# 3V3.net
KiCad netlist of a schematic drawn in Altium Designer
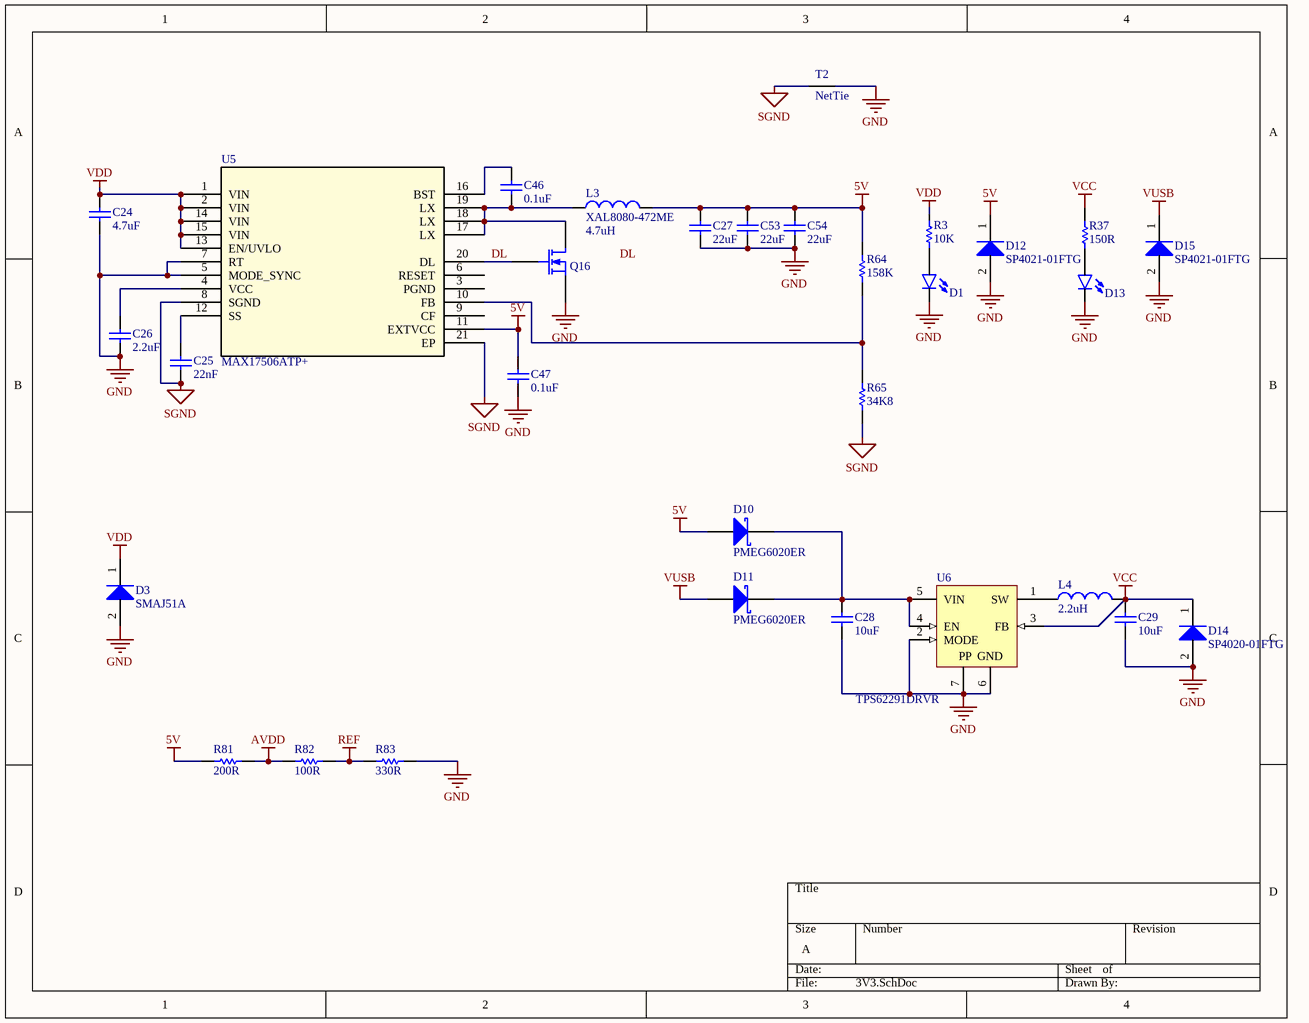
[diagram p0: 3V3.SchDoc]

(export (version "E")
  (design (tool "Eeschema 10.0.6"))
  (components
    (comp (ref "C24")
      (value "4.7uF")
      (footprint "C1210[3225X200]")
      (description "4.7uF 100V 10% 1210 (3225 Metric)")
      (fields (field (name "PARTNUMBER") "GRJ32DC72A475KE11L") (field (name "MANUFACTURER") "Murata"))
      (libsource (lib "Capacitors") (part "CAP_4.7uF_100V_1210_10%"))
    )
    (comp (ref "C25")
      (value "22nF")
      (footprint "C0603[1608X92]")
      (description "22nF 50V 10% 0603 (1608 Metric)")
      (fields (field (name "PARTNUMBER") "GRM188R71H223KA01D") (field (name "MANUFACTURER") "Murata"))
      (libsource (lib "Capacitors") (part "CAP_22nF_50V_0603_10%"))
    )
    (comp (ref "C26")
      (value "2.2uF")
      (footprint "C0603[1608X92]")
      (description "2.2uF 10V 10% 0603 (1608 Metric)")
      (fields (field (name "PARTNUMBER") "GRT188R61A225KE13D") (field (name "MANUFACTURER") "Murata"))
      (libsource (lib "Capacitors") (part "CAP_2.2uF_10V_0603_10%"))
    )
    (comp (ref "C27")
      (value "22uF")
      (footprint "C1210[3225X250]")
      (description "22uF 16V 20% 1210 (3225 Metric)")
      (fields (field (name "PARTNUMBER") "GRM32ER61C476ME15L") (field (name "MANUFACTURER") "Murata"))
      (libsource (lib "Capacitors") (part "CAP_22uF_16V_1210_20%"))
    )
    (comp (ref "C28")
      (value "10uF")
      (footprint "C0603[1608X92]")
      (description "10uF 16V 10% 0603 (1608 Metric)")
      (fields (field (name "PARTNUMBER") "GRM188R61C106KAALD") (field (name "MANUFACTURER") "Murata"))
      (libsource (lib "Capacitors") (part "CAP_10uF_16V_0603_10%"))
    )
    (comp (ref "C29")
      (value "10uF")
      (footprint "C0603[1608X92]")
      (description "10uF 6.3V 10% 0603 (1608 Metric)")
      (fields (field (name "PARTNUMBER") "GRM188R60J106KE47D") (field (name "MANUFACTURER") "Murata"))
      (libsource (lib "Capacitors") (part "CAP_10uF_6.3V_0603_10%"))
    )
    (comp (ref "C46")
      (value "0.1uF")
      (footprint "C0603[1608X92]")
      (description "0.1uF 16V 10% 0603 (1608 Metric)")
      (fields (field (name "PARTNUMBER") "GCM188R71C104KA37D") (field (name "MANUFACTURER") "Murata"))
      (libsource (lib "Capacitors") (part "CAP_0.1uF_16V_0603_10%"))
    )
    (comp (ref "C47")
      (value "0.1uF")
      (footprint "C0603[1608X92]")
      (description "0.1uF 6.3V 10% 0603 (1608 Metric)")
      (fields (field (name "PARTNUMBER") "GRM188R70J104KA01D") (field (name "MANUFACTURER") "Murata"))
      (libsource (lib "Capacitors") (part "CAP_0.1uF_6.3V_0603_10%"))
    )
    (comp (ref "C53")
      (value "22uF")
      (footprint "C1210[3225X250]")
      (description "22uF 16V 20% 1210 (3225 Metric)")
      (fields (field (name "PARTNUMBER") "GRM32ER61C476ME15L") (field (name "MANUFACTURER") "Murata"))
      (libsource (lib "Capacitors") (part "CAP_22uF_16V_1210_20%"))
    )
    (comp (ref "C54")
      (value "22uF")
      (footprint "C1210[3225X250]")
      (description "22uF 16V 20% 1210 (3225 Metric)")
      (fields (field (name "PARTNUMBER") "GRM32ER61C476ME15L") (field (name "MANUFACTURER") "Murata"))
      (libsource (lib "Capacitors") (part "CAP_22uF_16V_1210_20%"))
    )
    (comp (ref "D1")
      (value "LED_0603_GREEN_5mA")
      (footprint "LED0603")
      (fields (field (name "PARTNUMBER") "LTST-C193TGKT-5A") (field (name "MANUFACTURER") "Lite-On Inc."))
      (libsource (lib "LEDs") (part "LED_0603_GREEN_5mA"))
    )
    (comp (ref "D3")
      (value "SMAJ51A")
      (footprint "DO-214AC")
      (fields (field (name "PARTNUMBER") "SMAJ51A-E3/61") (field (name "MANUFACTURER") "Vishay"))
      (libsource (lib "Diodes") (part "SMAJ51A-E3/61"))
    )
    (comp (ref "D10")
      (value "PMEG6020ER")
      (footprint "SOD-123")
      (fields (field (name "PARTNUMBER") "PMEG6020ER,115") (field (name "MANUFACTURER") "NXP Semiconductors"))
      (libsource (lib "Diodes") (part "PMEG6020ER"))
    )
    (comp (ref "D11")
      (value "PMEG6020ER")
      (footprint "SOD-123")
      (fields (field (name "PARTNUMBER") "PMEG6020ER,115") (field (name "MANUFACTURER") "NXP Semiconductors"))
      (libsource (lib "Diodes") (part "PMEG6020ER"))
    )
    (comp (ref "D12")
      (value "SP4021-01FTG")
      (footprint "SOD-323")
      (fields (field (name "MANUFACTURER") "Littelfuse"))
      (libsource (lib "Diodes") (part "SP4021-01FTG"))
    )
    (comp (ref "D13")
      (value "LED_0603_GREEN_5mA")
      (footprint "LED0603")
      (fields (field (name "PARTNUMBER") "LTST-C193TGKT-5A") (field (name "MANUFACTURER") "Lite-On Inc."))
      (libsource (lib "LEDs") (part "LED_0603_GREEN_5mA"))
    )
    (comp (ref "D14")
      (value "SP4020-01FTG")
      (footprint "SOD-323")
      (fields (field (name "MANUFACTURER") "Littelfuse"))
      (libsource (lib "Diodes") (part "SP4020-01FTG"))
    )
    (comp (ref "D15")
      (value "SP4021-01FTG")
      (footprint "SOD-323")
      (fields (field (name "MANUFACTURER") "Littelfuse"))
      (libsource (lib "Diodes-TVS") (part "SP4021-01FTG"))
    )
    (comp (ref "L3")
      (value "XAL8080-472ME")
      (footprint "XAL8080")
      (description "4.7uH 38A 4.08mOhms")
      (fields
        (field (name "ALTIUM_VALUE") "4.7uH")
        (field (name "PARTNUMBER") "XAL8080-472MED")
        (field (name "MANUFACTURER") "Coilcraft")
        (field (name "PUBLISHER") "Altium Limited")
      )
      (libsource (lib "General_Component") (part "XAL8080-472ME"))
    )
    (comp (ref "L4")
      (value "2.2uH")
      (footprint "IND0805")
      (description "2.2uH 20% 1.7A 0805")
      (fields (field (name "PARTNUMBER") "LQM21PN2R2MGHL") (field (name "MANUFACTURER") "Murata"))
      (libsource (lib "Inductors") (part "IND_2.2uH_1.7A_0805_20%"))
    )
    (comp (ref "Q16")
      (value "SIS862DN-T1-GE3")
      (footprint "PowerPak-1212-8")
      (description "N-Channel MOSFET")
      (fields (field (name "MANUFACTURER") "Vishay"))
      (libsource (lib "MOSFETs") (part "SIS862DN-T1-GE3"))
    )
    (comp (ref "R3")
      (value "10K")
      (footprint "R0603[1608]")
      (description "10K 0.25W 1% 0603 (1005 Metric)")
      (fields (field (name "TOLERANCE") "1%") (field (name "POWER") "0.25W"))
      (libsource (lib "Resistors") (part "RES_10K_0603_1%"))
    )
    (comp (ref "R37")
      (value "150R")
      (footprint "R0603[1608]")
      (description "150R 0.25W 1% 0603 (1005 Metric)")
      (fields (field (name "MANUFACTURER") "Vishay / Dale") (field (name "PARTNUMBER") "CRCW0603150RFKEAHP"))
      (libsource (lib "Resistors") (part "RES_150R_0603_1%"))
    )
    (comp (ref "R64")
      (value "158K")
      (footprint "R0603[1608]")
      (description "158K 0.25W 1% 0603 (1005 Metric)")
      (fields (field (name "MANUFACTURER") "Vishay / Dale") (field (name "PARTNUMBER") "CRCW0603158KFKEAHP"))
      (libsource (lib "Resistors") (part "RES_158K_0603_1%"))
    )
    (comp (ref "R65")
      (value "34K8")
      (footprint "R0603[1608]")
      (description "34K8 0.25W 1% 0603 (1005 Metric)")
      (fields (field (name "MANUFACTURER") "Vishay / Dale") (field (name "PARTNUMBER") "CRCW060334K8FKEAHP"))
      (libsource (lib "Resistors") (part "RES_34K8_0603_1%"))
    )
    (comp (ref "R81")
      (value "200R")
      (footprint "R0603[1608]")
      (description "200R 0.25W 1% 0603 (1005 Metric)")
      (fields (field (name "MANUFACTURER") "Vishay / Dale") (field (name "PARTNUMBER") "CRCW0603200RFKEAHP"))
      (libsource (lib "Resistors") (part "RES_200R_0603_1%"))
    )
    (comp (ref "R82")
      (value "100R")
      (footprint "R0603[1608]")
      (description "100R 0.25W 1% 0603 (1005 Metric)")
      (fields (field (name "MANUFACTURER") "Vishay / Dale") (field (name "PARTNUMBER") "CRCW0603100RFKEAHP"))
      (libsource (lib "Resistors") (part "RES_100R_0603_1%"))
    )
    (comp (ref "R83")
      (value "330R")
      (footprint "R0603[1608]")
      (description "330R 0.25W 1% 0603 (1005 Metric)")
      (fields (field (name "MANUFACTURER") "Vishay / Dale") (field (name "PARTNUMBER") "CRCW0603330RFKEAHP"))
      (libsource (lib "Resistors") (part "RES_330R_0603_1%"))
    )
    (comp (ref "T2") (value "NetTie") (footprint "NetTie") (libsource (lib "Components") (part "NetTie")))
    (comp (ref "U5")
      (value "MAX17506ATP+")
      (footprint "21-0140L_T2055-4")
      (fields (field (name "MANUFACTURER") "Maxim"))
      (libsource (lib "General_Component") (part "MAX17506ATP+"))
    )
    (comp (ref "U6")
      (value "TPS62291DRVR")
      (footprint "WSON-6")
      (description "Voltage Regulators - Switching Regulators 2.25MHz 1A Step-Down Cnvrtr 3.3V Output")
      (fields (field (name "MANUFACTURER") "Texas Instruments"))
      (libsource (lib "ICs") (part "TPS62291DRVR"))
    )
  )
  (nets
    (net (code "1") (name "/DL") (class "Default")
      (node (ref "Q16") (pin "2") (pinfunction "G_2") (pintype "passive"))
      (node (ref "U5") (pin "20") (pinfunction "DL_20") (pintype "passive"))
    )
    (net (code "2") (name "5V") (class "Default")
      (node (ref "C27") (pin "2") (pinfunction "2_2") (pintype "passive"))
      (node (ref "C47") (pin "2") (pinfunction "2_2") (pintype "passive"))
      (node (ref "C53") (pin "2") (pinfunction "2_2") (pintype "passive"))
      (node (ref "C54") (pin "2") (pinfunction "2_2") (pintype "passive"))
      (node (ref "D10") (pin "2") (pinfunction "A_2") (pintype "passive"))
      (node (ref "D12") (pin "1") (pinfunction "K_1") (pintype "passive"))
      (node (ref "L3") (pin "2") (pinfunction "2_2") (pintype "passive"))
      (node (ref "R64") (pin "2") (pinfunction "2_2") (pintype "passive"))
      (node (ref "R81") (pin "1") (pinfunction "1_1") (pintype "passive"))
      (node (ref "U5") (pin "11") (pinfunction "EXTVCC_11") (pintype "passive"))
    )
    (net (code "3") (name "AVDD") (class "Default")
      (node (ref "R81") (pin "2") (pinfunction "2_2") (pintype "passive"))
      (node (ref "R82") (pin "1") (pinfunction "1_1") (pintype "passive"))
    )
    (net (code "4") (name "GND") (class "Default")
      (node (ref "C24") (pin "1") (pinfunction "1_1") (pintype "passive"))
      (node (ref "C26") (pin "1") (pinfunction "1_1") (pintype "passive"))
      (node (ref "C27") (pin "1") (pinfunction "1_1") (pintype "passive"))
      (node (ref "C28") (pin "1") (pinfunction "1_1") (pintype "passive"))
      (node (ref "C29") (pin "1") (pinfunction "1_1") (pintype "passive"))
      (node (ref "C47") (pin "1") (pinfunction "1_1") (pintype "passive"))
      (node (ref "C53") (pin "1") (pinfunction "1_1") (pintype "passive"))
      (node (ref "C54") (pin "1") (pinfunction "1_1") (pintype "passive"))
      (node (ref "D1") (pin "C") (pinfunction "C_C") (pintype "passive"))
      (node (ref "D12") (pin "2") (pinfunction "A_2") (pintype "passive"))
      (node (ref "D13") (pin "C") (pinfunction "C_C") (pintype "passive"))
      (node (ref "D14") (pin "2") (pinfunction "A_2") (pintype "passive"))
      (node (ref "D15") (pin "2") (pinfunction "A_2") (pintype "passive"))
      (node (ref "D3") (pin "2") (pinfunction "A_2") (pintype "passive"))
      (node (ref "Q16") (pin "1") (pinfunction "S_1") (pintype "passive"))
      (node (ref "R83") (pin "2") (pinfunction "2_2") (pintype "passive"))
      (node (ref "T2") (pin "2") (pinfunction "2_2") (pintype "passive"))
      (node (ref "U5") (pin "5") (pinfunction "MODE_SYNC_5") (pintype "passive"))
      (node (ref "U5") (pin "7") (pinfunction "RT_7") (pintype "passive"))
      (node (ref "U6") (pin "2") (pinfunction "MODE_2") (pintype "input"))
      (node (ref "U6") (pin "6") (pinfunction "GND_6") (pintype "power_in"))
      (node (ref "U6") (pin "7") (pinfunction "EP_7") (pintype "passive"))
    )
    (net (code "5") (name "Net-(D1-PadA)") (class "Default")
      (node (ref "D1") (pin "A") (pinfunction "A_A") (pintype "passive"))
      (node (ref "R3") (pin "1") (pinfunction "1_1") (pintype "passive"))
    )
    (net (code "6") (name "Net-(D10-K)") (class "Default")
      (node (ref "C28") (pin "2") (pinfunction "2_2") (pintype "passive"))
      (node (ref "D10") (pin "1") (pinfunction "K_1") (pintype "passive"))
      (node (ref "D11") (pin "1") (pinfunction "K_1") (pintype "passive"))
      (node (ref "U6") (pin "4") (pinfunction "EN_4") (pintype "input"))
      (node (ref "U6") (pin "5") (pinfunction "VIN_5") (pintype "power_in"))
    )
    (net (code "7") (name "Net-(D13-PadA)") (class "Default")
      (node (ref "D13") (pin "A") (pinfunction "A_A") (pintype "passive"))
      (node (ref "R37") (pin "1") (pinfunction "1_1") (pintype "passive"))
    )
    (net (code "8") (name "Net-(Q16-D)") (class "Default")
      (node (ref "C46") (pin "1") (pinfunction "1_1") (pintype "passive"))
      (node (ref "L3") (pin "1") (pinfunction "1_1") (pintype "passive"))
      (node (ref "Q16") (pin "3") (pinfunction "D_3") (pintype "passive"))
      (node (ref "U5") (pin "17") (pinfunction "LX_17") (pintype "passive"))
      (node (ref "U5") (pin "18") (pinfunction "LX_18") (pintype "passive"))
      (node (ref "U5") (pin "19") (pinfunction "LX_19") (pintype "passive"))
    )
    (net (code "9") (name "Net-(U5-BST)") (class "Default")
      (node (ref "C46") (pin "2") (pinfunction "2_2") (pintype "passive"))
      (node (ref "U5") (pin "16") (pinfunction "BST_16") (pintype "passive"))
    )
    (net (code "10") (name "Net-(U5-FB)") (class "Default")
      (node (ref "R64") (pin "1") (pinfunction "1_1") (pintype "passive"))
      (node (ref "R65") (pin "2") (pinfunction "2_2") (pintype "passive"))
      (node (ref "U5") (pin "10") (pinfunction "FB_10") (pintype "passive"))
    )
    (net (code "11") (name "Net-(U5-SS)") (class "Default")
      (node (ref "C25") (pin "2") (pinfunction "2_2") (pintype "passive"))
      (node (ref "U5") (pin "12") (pinfunction "SS_12") (pintype "passive"))
    )
    (net (code "12") (name "Net-(U5-VCC)") (class "Default")
      (node (ref "C26") (pin "2") (pinfunction "2_2") (pintype "passive"))
      (node (ref "U5") (pin "4") (pinfunction "VCC_4") (pintype "power_in"))
    )
    (net (code "13") (name "Net-(U6-SW)") (class "Default")
      (node (ref "L4") (pin "1") (pinfunction "1_1") (pintype "passive"))
      (node (ref "U6") (pin "1") (pinfunction "SW_1") (pintype "power_in"))
    )
    (net (code "14") (name "REF") (class "Default")
      (node (ref "R82") (pin "2") (pinfunction "2_2") (pintype "passive"))
      (node (ref "R83") (pin "1") (pinfunction "1_1") (pintype "passive"))
    )
    (net (code "15") (name "SGND") (class "Default")
      (node (ref "C25") (pin "1") (pinfunction "1_1") (pintype "passive"))
      (node (ref "R65") (pin "1") (pinfunction "1_1") (pintype "passive"))
      (node (ref "T2") (pin "1") (pinfunction "1_1") (pintype "passive"))
      (node (ref "U5") (pin "21") (pinfunction "EP_21") (pintype "passive"))
      (node (ref "U5") (pin "8") (pinfunction "SGND_8") (pintype "power_in"))
    )
    (net (code "16") (name "VCC") (class "Default")
      (node (ref "C29") (pin "2") (pinfunction "2_2") (pintype "passive"))
      (node (ref "D14") (pin "1") (pinfunction "K_1") (pintype "passive"))
      (node (ref "L4") (pin "2") (pinfunction "2_2") (pintype "passive"))
      (node (ref "R37") (pin "2") (pinfunction "2_2") (pintype "passive"))
      (node (ref "U6") (pin "3") (pinfunction "FB_3") (pintype "input"))
    )
    (net (code "17") (name "VDD") (class "Default")
      (node (ref "C24") (pin "2") (pinfunction "2_2") (pintype "passive"))
      (node (ref "D3") (pin "1") (pinfunction "K_1") (pintype "passive"))
      (node (ref "R3") (pin "2") (pinfunction "2_2") (pintype "passive"))
      (node (ref "U5") (pin "1") (pinfunction "VIN_1") (pintype "passive"))
      (node (ref "U5") (pin "13") (pinfunction "EN/UVLO_13") (pintype "passive"))
      (node (ref "U5") (pin "14") (pinfunction "VIN_14") (pintype "passive"))
      (node (ref "U5") (pin "15") (pinfunction "VIN_15") (pintype "passive"))
      (node (ref "U5") (pin "2") (pinfunction "VIN_2") (pintype "passive"))
    )
    (net (code "18") (name "VUSB") (class "Default")
      (node (ref "D11") (pin "2") (pinfunction "A_2") (pintype "passive"))
      (node (ref "D15") (pin "1") (pinfunction "K_1") (pintype "passive"))
    )
    (net (code "19") (name "unconnected-(U5-CF-Pad9)") (class "Default")
      (node (ref "U5") (pin "9") (pinfunction "CF_9") (pintype "passive"))
    )
    (net (code "20") (name "unconnected-(U5-PGND-Pad3)") (class "Default")
      (node (ref "U5") (pin "3") (pinfunction "PGND_3") (pintype "passive"))
    )
    (net (code "21") (name "unconnected-(U5-RESET-Pad6)") (class "Default")
      (node (ref "U5") (pin "6") (pinfunction "RESET_6") (pintype "passive"))
    )
  )
)
